# 1.net
KiCad netlist of a schematic drawn in EAGLE
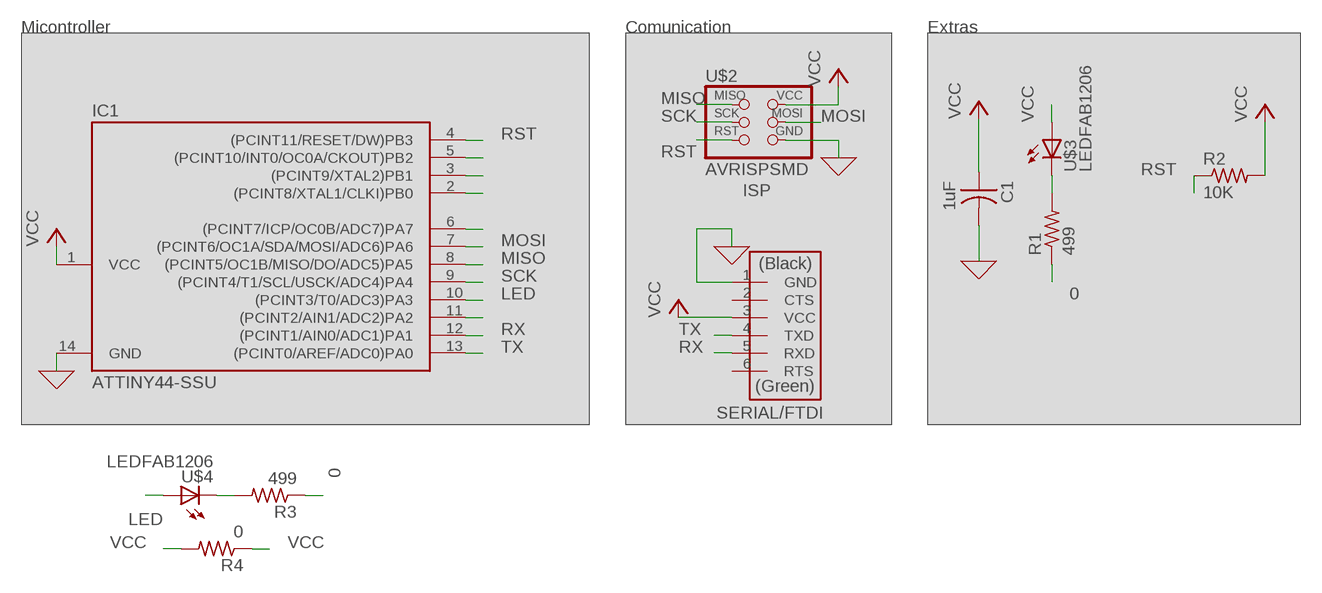
[diagram p0: schematic, sheet 1]

(export (version "E")
  (design (tool "Eeschema 10.0.6"))
  (components
    (comp (ref "C1")
      (value "1uF")
      (footprint "eagle-import:C1206FAB")
      (libsource (lib "eagle-import") (part "CAP-US1206FAB"))
    )
    (comp (ref "IC1")
      (value "ATTINY44-SSU")
      (footprint "eagle-import:SOIC14")
      (libsource (lib "eagle-import") (part "ATTINY44-SSU"))
    )
    (comp (ref "R1")
      (value "499")
      (footprint "eagle-import:R1206FAB")
      (libsource (lib "eagle-import") (part "RES-US1206FAB"))
    )
    (comp (ref "R2")
      (value "10K")
      (footprint "eagle-import:R1206FAB")
      (libsource (lib "eagle-import") (part "RES-US1206FAB"))
    )
    (comp (ref "R3")
      (value "499")
      (footprint "eagle-import:R1206FAB")
      (libsource (lib "eagle-import") (part "RES-US1206FAB"))
    )
    (comp (ref "R4")
      (value "0")
      (footprint "eagle-import:R1206FAB")
      (libsource (lib "eagle-import") (part "RES-US1206FAB"))
    )
    (comp (ref "U$1")
      (value "FTDI-SMD-HEADER")
      (footprint "eagle-import:1X06SMD")
      (libsource (lib "eagle-import") (part "FTDI-SMD-HEADER"))
    )
    (comp (ref "U$2")
      (value "AVRISPSMD")
      (footprint "eagle-import:2X03SMD")
      (libsource (lib "eagle-import") (part "AVRISPSMD"))
    )
    (comp (ref "U$3")
      (value "LEDFAB1206")
      (footprint "eagle-import:LED1206FAB")
      (libsource (lib "eagle-import") (part "LEDFAB1206"))
    )
    (comp (ref "U$4")
      (value "LEDFAB1206")
      (footprint "eagle-import:LED1206FAB")
      (libsource (lib "eagle-import") (part "LEDFAB1206"))
    )
  )
  (nets
    (net (code "1") (name "/LED") (class "Default")
      (node (ref "IC1") (pin "10") (pinfunction "(PCINT3/T0/ADC3)PA3_10") (pintype "bidirectional"))
      (node (ref "U$4") (pin "1") (pinfunction "A_1") (pintype "passive"))
    )
    (net (code "2") (name "/MISO") (class "Default")
      (node (ref "IC1") (pin "6") (pinfunction "(PCINT7/ICP/OC0B/ADC7)PA7_6") (pintype "bidirectional"))
      (node (ref "IC1") (pin "8") (pinfunction "(PCINT5/OC1B/MISO/DO/ADC5)PA5_8") (pintype "bidirectional"))
      (node (ref "U$2") (pin "1") (pinfunction "MISO_1") (pintype "passive"))
    )
    (net (code "3") (name "/MOSI") (class "Default")
      (node (ref "IC1") (pin "7") (pinfunction "(PCINT6/OC1A/SDA/MOSI/ADC6)PA6_7") (pintype "bidirectional"))
      (node (ref "U$2") (pin "4") (pinfunction "MOSI_4") (pintype "passive"))
    )
    (net (code "4") (name "/RST") (class "Default")
      (node (ref "IC1") (pin "4") (pinfunction "(PCINT11/RESET/DW)PB3_4") (pintype "bidirectional"))
      (node (ref "R2") (pin "1") (pinfunction "1_1") (pintype "passive"))
      (node (ref "U$2") (pin "5") (pinfunction "RST_5") (pintype "passive"))
    )
    (net (code "5") (name "/RX") (class "Default")
      (node (ref "IC1") (pin "12") (pinfunction "(PCINT1/AIN0/ADC1)PA1_12") (pintype "bidirectional"))
      (node (ref "U$1") (pin "5") (pinfunction "RXD_5") (pintype "bidirectional"))
    )
    (net (code "6") (name "/SCK") (class "Default")
      (node (ref "IC1") (pin "9") (pinfunction "(PCINT4/T1/SCL/USCK/ADC4)PA4_9") (pintype "bidirectional"))
      (node (ref "U$2") (pin "3") (pinfunction "SCK_3") (pintype "passive"))
    )
    (net (code "7") (name "/TX") (class "Default")
      (node (ref "IC1") (pin "13") (pinfunction "(PCINT0/AREF/ADC0)PA0_13") (pintype "bidirectional"))
      (node (ref "U$1") (pin "4") (pinfunction "TXD_4") (pintype "bidirectional"))
    )
    (net (code "8") (name "GND") (class "Default")
      (node (ref "C1") (pin "2") (pinfunction "2_2") (pintype "passive"))
      (node (ref "IC1") (pin "14") (pinfunction "GND_14") (pintype "power_in"))
      (node (ref "R1") (pin "1") (pinfunction "1_1") (pintype "passive"))
      (node (ref "R3") (pin "1") (pinfunction "1_1") (pintype "passive"))
      (node (ref "U$1") (pin "1") (pinfunction "GND_1") (pintype "bidirectional"))
      (node (ref "U$2") (pin "6") (pinfunction "GND_6") (pintype "passive"))
    )
    (net (code "9") (name "Net-(U$3-C)") (class "Default")
      (node (ref "R1") (pin "2") (pinfunction "2_2") (pintype "passive"))
      (node (ref "U$3") (pin "2") (pinfunction "C_2") (pintype "passive"))
    )
    (net (code "10") (name "Net-(U$4-C)") (class "Default")
      (node (ref "R3") (pin "2") (pinfunction "2_2") (pintype "passive"))
      (node (ref "U$4") (pin "2") (pinfunction "C_2") (pintype "passive"))
    )
    (net (code "11") (name "VCC") (class "Default")
      (node (ref "C1") (pin "1") (pinfunction "1_1") (pintype "passive"))
      (node (ref "IC1") (pin "1") (pinfunction "VCC_1") (pintype "power_in"))
      (node (ref "R2") (pin "2") (pinfunction "2_2") (pintype "passive"))
      (node (ref "R4") (pin "1") (pinfunction "1_1") (pintype "passive"))
      (node (ref "R4") (pin "2") (pinfunction "2_2") (pintype "passive"))
      (node (ref "U$1") (pin "3") (pinfunction "VCC_3") (pintype "bidirectional"))
      (node (ref "U$2") (pin "2") (pinfunction "VCC_2") (pintype "passive"))
      (node (ref "U$3") (pin "1") (pinfunction "A_1") (pintype "passive"))
    )
    (net (code "12") (name "unconnected-(IC1-(PCINT2{slash}AIN1{slash}ADC2)PA2-Pad11)") (class "Default")
      (node (ref "IC1") (pin "11") (pinfunction "(PCINT2/AIN1/ADC2)PA2_11") (pintype "bidirectional"))
    )
    (net (code "13") (name "unconnected-(IC1-(PCINT8{slash}XTAL1{slash}CLKI)PB0-Pad2)") (class "Default")
      (node (ref "IC1") (pin "2") (pinfunction "(PCINT8/XTAL1/CLKI)PB0_2") (pintype "bidirectional"))
    )
    (net (code "14") (name "unconnected-(IC1-(PCINT9{slash}XTAL2)PB1-Pad3)") (class "Default")
      (node (ref "IC1") (pin "3") (pinfunction "(PCINT9/XTAL2)PB1_3") (pintype "bidirectional"))
    )
    (net (code "15") (name "unconnected-(IC1-(PCINT10{slash}INT0{slash}OC0A{slash}CKOUT)PB2-Pad5)") (class "Default")
      (node (ref "IC1") (pin "5") (pinfunction "(PCINT10/INT0/OC0A/CKOUT)PB2_5") (pintype "bidirectional"))
    )
    (net (code "16") (name "unconnected-(U$1-CTS-Pad2)") (class "Default")
      (node (ref "U$1") (pin "2") (pinfunction "CTS_2") (pintype "bidirectional"))
    )
    (net (code "17") (name "unconnected-(U$1-RTS-Pad6)") (class "Default")
      (node (ref "U$1") (pin "6") (pinfunction "RTS_6") (pintype "bidirectional"))
    )
  )
)
